# SCH_555-circuit_2025-03-19.net
KiCad netlist of a schematic drawn in EasyEDA
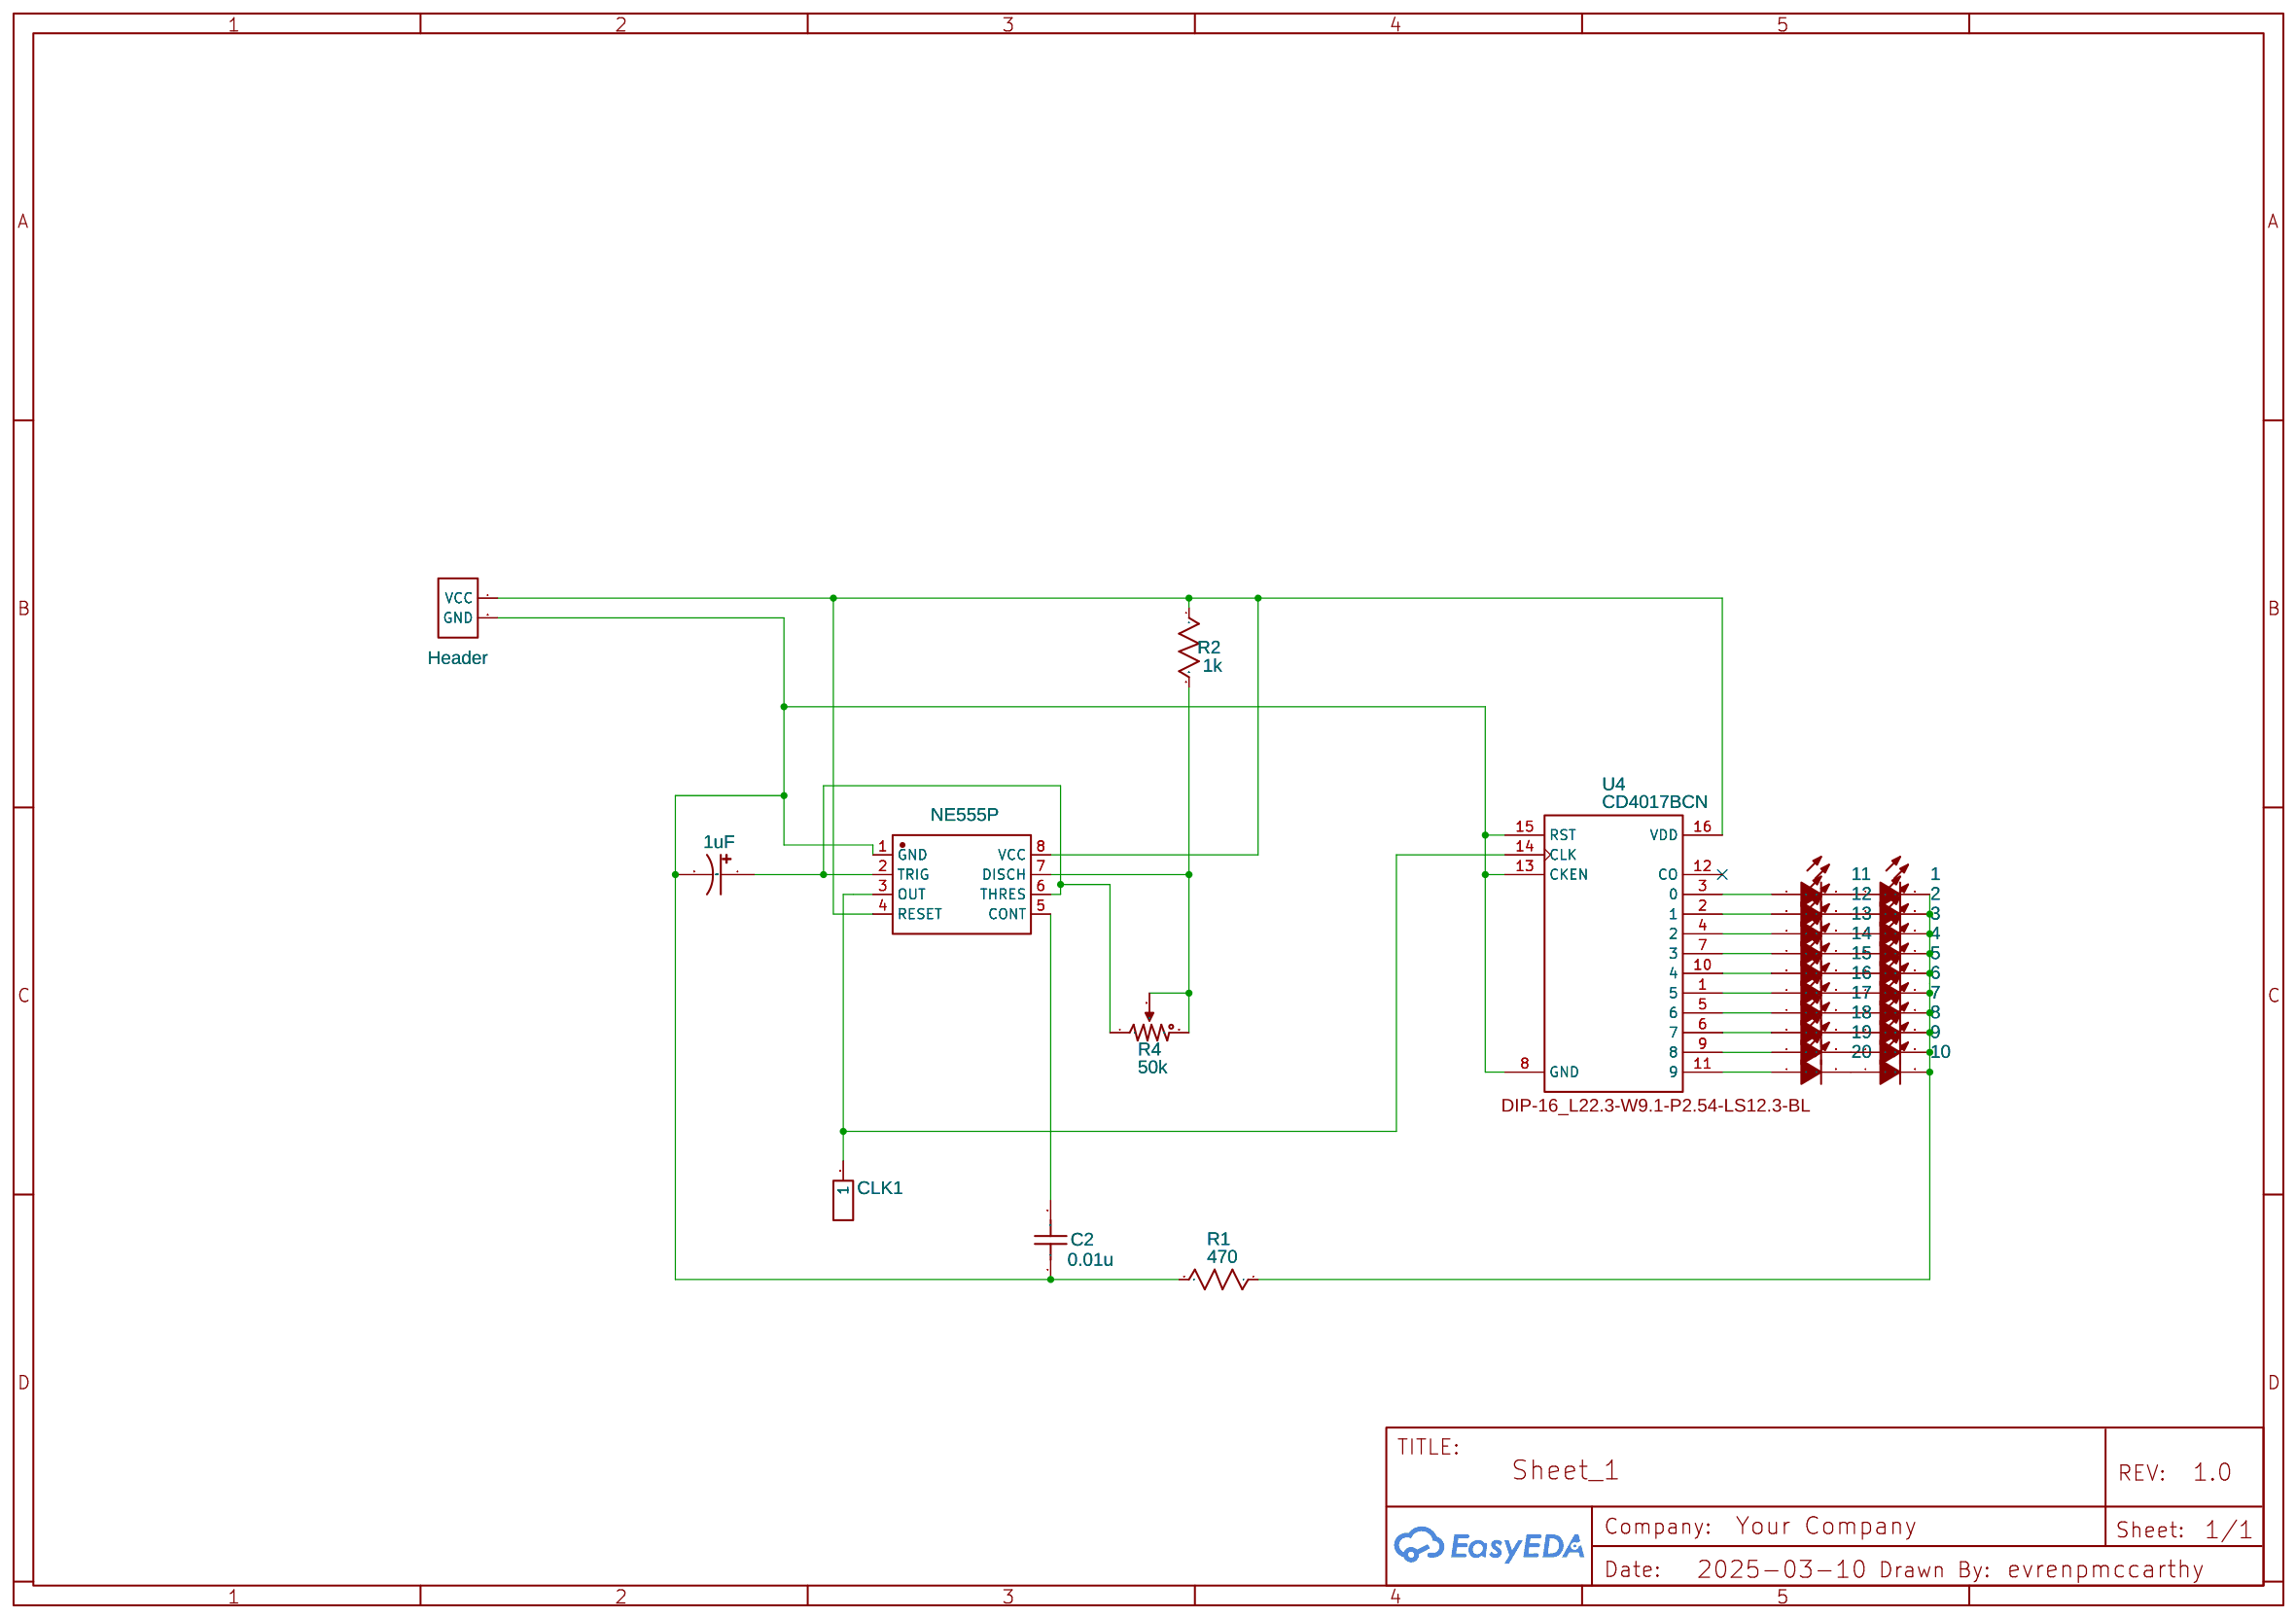
[diagram p0: schematic sheet]

(export (version "E")
  (design (tool "Eeschema 10.0.6"))
  (components
    (comp (ref "1") (value "LED_5MM") (libsource (lib "") (part "LED_5MM")))
    (comp (ref "2") (value "LED_5MM") (libsource (lib "") (part "LED_5MM")))
    (comp (ref "3") (value "LED_5MM") (libsource (lib "") (part "LED_5MM")))
    (comp (ref "4") (value "LED_5MM") (libsource (lib "") (part "LED_5MM")))
    (comp (ref "5") (value "LED_5MM") (libsource (lib "") (part "LED_5MM")))
    (comp (ref "6") (value "LED_5MM") (libsource (lib "") (part "LED_5MM")))
    (comp (ref "7") (value "LED_5MM") (libsource (lib "") (part "LED_5MM")))
    (comp (ref "8") (value "LED_5MM") (libsource (lib "") (part "LED_5MM")))
    (comp (ref "9") (value "LED_5MM") (libsource (lib "") (part "LED_5MM")))
    (comp (ref "10") (value "LED_5MM") (libsource (lib "") (part "LED_5MM")))
    (comp (ref "11") (value "LED_5MM") (libsource (lib "") (part "LED_5MM")))
    (comp (ref "12") (value "LED_5MM") (libsource (lib "") (part "LED_5MM")))
    (comp (ref "13") (value "LED_5MM") (libsource (lib "") (part "LED_5MM")))
    (comp (ref "14") (value "LED_5MM") (libsource (lib "") (part "LED_5MM")))
    (comp (ref "15") (value "LED_5MM") (libsource (lib "") (part "LED_5MM")))
    (comp (ref "16") (value "LED_5MM") (libsource (lib "") (part "LED_5MM")))
    (comp (ref "17") (value "LED_5MM") (libsource (lib "") (part "LED_5MM")))
    (comp (ref "18") (value "LED_5MM") (libsource (lib "") (part "LED_5MM")))
    (comp (ref "19") (value "LED_5MM") (libsource (lib "") (part "LED_5MM")))
    (comp (ref "20") (value "LED_5MM") (libsource (lib "") (part "LED_5MM")))
    (comp (ref "C1")
      (value "1uF")
      (fields (field (name "Manufacturer Part") "UVZ1H010MDD") (field (name "Manufacturer") "Nichicon(尼吉康)"))
      (libsource (lib "") (part "UVZ1H010MDD"))
    )
    (comp (ref "C2") (value "0.01u") (libsource (lib "") (part "C_0603_US")))
    (comp (ref "CLK1")
      (value "C81276")
      (fields
        (field (name "Manufacturer Part") "2.54-1*1P针")
        (field (name "Manufacturer") "BOOMELE(Boom Precision Elec)")
      )
      (libsource (lib "") (part "Header-Male-2.54_1x1"))
    )
    (comp (ref "H1") (value "Header") (libsource (lib "") (part "HEADER-FEMALE-2.54_1X2")))
    (comp (ref "R1")
      (value "470")
      (fields (field (name "Manufacturer Part") "?"))
      (libsource (lib "") (part "Resistor_1"))
    )
    (comp (ref "R2")
      (value "1k")
      (fields (field (name "Manufacturer Part") "?"))
      (libsource (lib "") (part "Resistor"))
    )
    (comp (ref "R4")
      (value "50k")
      (fields (field (name "Manufacturer Part") "?"))
      (libsource (lib "") (part "Potentiometer"))
    )
    (comp (ref "U2")
      (value "NE555P")
      (fields (field (name "Manufacturer") "TI(德州仪器)"))
      (libsource (lib "") (part "NE555P"))
    )
    (comp (ref "U4") (value "CD4017BCN") (libsource (lib "") (part "CD4017BCN")))
  )
  (nets
    (net (code "1") (name "Net-(1-A)") (class "Default")
      (node (ref "1") (pin "1") (pinfunction "A_1") (pintype "input"))
      (node (ref "11") (pin "2") (pinfunction "K_2") (pintype "input"))
    )
    (net (code "2") (name "Net-(1-K)") (class "Default")
      (node (ref "1") (pin "2") (pinfunction "K_2") (pintype "input"))
      (node (ref "10") (pin "2") (pinfunction "K_2") (pintype "input"))
      (node (ref "2") (pin "2") (pinfunction "K_2") (pintype "input"))
      (node (ref "3") (pin "2") (pinfunction "K_2") (pintype "input"))
      (node (ref "4") (pin "2") (pinfunction "K_2") (pintype "input"))
      (node (ref "5") (pin "2") (pinfunction "K_2") (pintype "input"))
      (node (ref "6") (pin "2") (pinfunction "K_2") (pintype "input"))
      (node (ref "7") (pin "2") (pinfunction "K_2") (pintype "input"))
      (node (ref "8") (pin "2") (pinfunction "K_2") (pintype "input"))
      (node (ref "9") (pin "2") (pinfunction "K_2") (pintype "input"))
      (node (ref "R1") (pin "1") (pinfunction "1_1") (pintype "unspecified"))
    )
    (net (code "3") (name "Net-(10-A)") (class "Default")
      (node (ref "10") (pin "1") (pinfunction "A_1") (pintype "input"))
      (node (ref "20") (pin "2") (pinfunction "K_2") (pintype "input"))
    )
    (net (code "4") (name "Net-(11-A)") (class "Default")
      (node (ref "11") (pin "1") (pinfunction "A_1") (pintype "input"))
      (node (ref "U4") (pin "3") (pinfunction "0_3") (pintype "output"))
    )
    (net (code "5") (name "Net-(12-A)") (class "Default")
      (node (ref "12") (pin "1") (pinfunction "A_1") (pintype "input"))
      (node (ref "U4") (pin "2") (pinfunction "1_2") (pintype "output"))
    )
    (net (code "6") (name "Net-(12-K)") (class "Default")
      (node (ref "12") (pin "2") (pinfunction "K_2") (pintype "input"))
      (node (ref "2") (pin "1") (pinfunction "A_1") (pintype "input"))
    )
    (net (code "7") (name "Net-(13-A)") (class "Default")
      (node (ref "13") (pin "1") (pinfunction "A_1") (pintype "input"))
      (node (ref "U4") (pin "4") (pinfunction "2_4") (pintype "output"))
    )
    (net (code "8") (name "Net-(13-K)") (class "Default")
      (node (ref "13") (pin "2") (pinfunction "K_2") (pintype "input"))
      (node (ref "3") (pin "1") (pinfunction "A_1") (pintype "input"))
    )
    (net (code "9") (name "Net-(14-A)") (class "Default")
      (node (ref "14") (pin "1") (pinfunction "A_1") (pintype "input"))
      (node (ref "U4") (pin "7") (pinfunction "3_7") (pintype "output"))
    )
    (net (code "10") (name "Net-(14-K)") (class "Default")
      (node (ref "14") (pin "2") (pinfunction "K_2") (pintype "input"))
      (node (ref "4") (pin "1") (pinfunction "A_1") (pintype "input"))
    )
    (net (code "11") (name "Net-(15-A)") (class "Default")
      (node (ref "15") (pin "1") (pinfunction "A_1") (pintype "input"))
      (node (ref "U4") (pin "10") (pinfunction "4_10") (pintype "output"))
    )
    (net (code "12") (name "Net-(15-K)") (class "Default")
      (node (ref "15") (pin "2") (pinfunction "K_2") (pintype "input"))
      (node (ref "5") (pin "1") (pinfunction "A_1") (pintype "input"))
    )
    (net (code "13") (name "Net-(16-A)") (class "Default")
      (node (ref "16") (pin "1") (pinfunction "A_1") (pintype "input"))
      (node (ref "U4") (pin "1") (pinfunction "5_1") (pintype "output"))
    )
    (net (code "14") (name "Net-(16-K)") (class "Default")
      (node (ref "16") (pin "2") (pinfunction "K_2") (pintype "input"))
      (node (ref "6") (pin "1") (pinfunction "A_1") (pintype "input"))
    )
    (net (code "15") (name "Net-(17-A)") (class "Default")
      (node (ref "17") (pin "1") (pinfunction "A_1") (pintype "input"))
      (node (ref "U4") (pin "5") (pinfunction "6_5") (pintype "output"))
    )
    (net (code "16") (name "Net-(17-K)") (class "Default")
      (node (ref "17") (pin "2") (pinfunction "K_2") (pintype "input"))
      (node (ref "7") (pin "1") (pinfunction "A_1") (pintype "input"))
    )
    (net (code "17") (name "Net-(18-A)") (class "Default")
      (node (ref "18") (pin "1") (pinfunction "A_1") (pintype "input"))
      (node (ref "U4") (pin "6") (pinfunction "7_6") (pintype "output"))
    )
    (net (code "18") (name "Net-(18-K)") (class "Default")
      (node (ref "18") (pin "2") (pinfunction "K_2") (pintype "input"))
      (node (ref "8") (pin "1") (pinfunction "A_1") (pintype "input"))
    )
    (net (code "19") (name "Net-(19-A)") (class "Default")
      (node (ref "19") (pin "1") (pinfunction "A_1") (pintype "input"))
      (node (ref "U4") (pin "9") (pinfunction "8_9") (pintype "output"))
    )
    (net (code "20") (name "Net-(19-K)") (class "Default")
      (node (ref "19") (pin "2") (pinfunction "K_2") (pintype "input"))
      (node (ref "9") (pin "1") (pinfunction "A_1") (pintype "input"))
    )
    (net (code "21") (name "Net-(20-A)") (class "Default")
      (node (ref "20") (pin "1") (pinfunction "A_1") (pintype "input"))
      (node (ref "U4") (pin "11") (pinfunction "9_11") (pintype "output"))
    )
    (net (code "22") (name "Net-(H1-GND)") (class "Default")
      (node (ref "C1") (pin "2") (pinfunction "2_2") (pintype "unspecified"))
      (node (ref "C2") (pin "1") (pinfunction "1_1") (pintype "unspecified"))
      (node (ref "H1") (pin "2") (pinfunction "GND_2") (pintype "unspecified"))
      (node (ref "R1") (pin "2") (pinfunction "2_2") (pintype "unspecified"))
      (node (ref "U2") (pin "1") (pinfunction "GND_1") (pintype "unspecified"))
      (node (ref "U4") (pin "13") (pinfunction "CKEN_13") (pintype "unspecified"))
      (node (ref "U4") (pin "15") (pinfunction "RST_15") (pintype "unspecified"))
      (node (ref "U4") (pin "8") (pinfunction "GND_8") (pintype "passive"))
    )
    (net (code "23") (name "Net-(H1-VCC)") (class "Default")
      (node (ref "H1") (pin "1") (pinfunction "VCC_1") (pintype "unspecified"))
      (node (ref "R2") (pin "1") (pinfunction "1_1") (pintype "unspecified"))
      (node (ref "U2") (pin "4") (pinfunction "RESET_4") (pintype "unspecified"))
      (node (ref "U2") (pin "8") (pinfunction "VCC_8") (pintype "unspecified"))
      (node (ref "U4") (pin "16") (pinfunction "VDD_16") (pintype "passive"))
    )
    (net (code "24") (name "Net-(R4-2)") (class "Default")
      (node (ref "R2") (pin "2") (pinfunction "2_2") (pintype "unspecified"))
      (node (ref "R4") (pin "2") (pinfunction "3_2") (pintype "unspecified"))
      (node (ref "R4") (pin "3") (pinfunction "2_3") (pintype "unspecified"))
      (node (ref "U2") (pin "7") (pinfunction "DISCH_7") (pintype "unspecified"))
    )
    (net (code "25") (name "Net-(U2-CONT)") (class "Default")
      (node (ref "C2") (pin "2") (pinfunction "2_2") (pintype "unspecified"))
      (node (ref "U2") (pin "5") (pinfunction "CONT_5") (pintype "unspecified"))
    )
    (net (code "26") (name "Net-(U2-OUT)") (class "Default")
      (node (ref "CLK1") (pin "1") (pinfunction "1_1") (pintype "unspecified"))
      (node (ref "U2") (pin "3") (pinfunction "OUT_3") (pintype "unspecified"))
      (node (ref "U4") (pin "14") (pinfunction "CLK_14") (pintype "unspecified"))
    )
    (net (code "27") (name "Net-(U2-THRES)") (class "Default")
      (node (ref "C1") (pin "1") (pinfunction "1_1") (pintype "unspecified"))
      (node (ref "R4") (pin "1") (pinfunction "1_1") (pintype "unspecified"))
      (node (ref "U2") (pin "2") (pinfunction "TRIG_2") (pintype "unspecified"))
      (node (ref "U2") (pin "6") (pinfunction "THRES_6") (pintype "unspecified"))
    )
    (net (code "28") (name "unconnected-(U4-CO-Pad12)") (class "Default")
      (node (ref "U4") (pin "12") (pinfunction "CO_12") (pintype "output+no_connect"))
    )
  )
)
